# v1.net
KiCad netlist of a schematic drawn in EAGLE
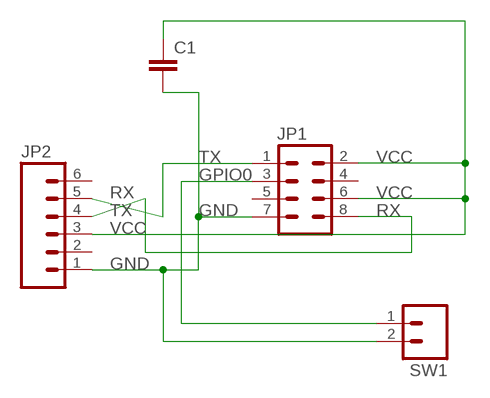
[diagram p0: schematic, sheet 1]

(export (version "E")
  (design (tool "Eeschema 10.0.6"))
  (components
    (comp (ref "C1")
      (value "CAP0805")
      (footprint "eagle-import:0805")
      (libsource (lib "eagle-import") (part "CAP0805"))
    )
    (comp (ref "JP1")
      (value "M04X2")
      (footprint "eagle-import:2X4")
      (libsource (lib "eagle-import") (part "M04X2"))
    )
    (comp (ref "JP2")
      (value "M06SILK_FEMALE_PTH")
      (footprint "eagle-import:1X06")
      (libsource (lib "eagle-import") (part "M06SILK_FEMALE_PTH"))
    )
    (comp (ref "SW1")
      (value "M02PTH")
      (footprint "eagle-import:1X02")
      (libsource (lib "eagle-import") (part "M02PTH"))
    )
  )
  (nets
    (net (code "1") (name "/GND") (class "Default")
      (node (ref "C1") (pin "2") (pinfunction "2_2") (pintype "passive"))
      (node (ref "JP1") (pin "7") (pinfunction "7_7") (pintype "passive"))
      (node (ref "JP2") (pin "1") (pinfunction "1_1") (pintype "passive"))
      (node (ref "SW1") (pin "2") (pinfunction "2_2") (pintype "passive"))
    )
    (net (code "2") (name "/GPIO0") (class "Default")
      (node (ref "JP1") (pin "3") (pinfunction "3_3") (pintype "passive"))
      (node (ref "SW1") (pin "1") (pinfunction "1_1") (pintype "passive"))
    )
    (net (code "3") (name "/RX") (class "Default")
      (node (ref "JP1") (pin "8") (pinfunction "8_8") (pintype "passive"))
      (node (ref "JP2") (pin "4") (pinfunction "4_4") (pintype "passive"))
    )
    (net (code "4") (name "/TX") (class "Default")
      (node (ref "JP1") (pin "1") (pinfunction "1_1") (pintype "passive"))
      (node (ref "JP2") (pin "5") (pinfunction "5_5") (pintype "passive"))
    )
    (net (code "5") (name "/VCC") (class "Default")
      (node (ref "C1") (pin "1") (pinfunction "1_1") (pintype "passive"))
      (node (ref "JP1") (pin "2") (pinfunction "2_2") (pintype "passive"))
      (node (ref "JP1") (pin "6") (pinfunction "6_6") (pintype "passive"))
      (node (ref "JP2") (pin "3") (pinfunction "3_3") (pintype "passive"))
    )
    (net (code "6") (name "unconnected-(JP1-Pad4)") (class "Default")
      (node (ref "JP1") (pin "4") (pinfunction "4_4") (pintype "passive"))
    )
    (net (code "7") (name "unconnected-(JP1-Pad5)") (class "Default")
      (node (ref "JP1") (pin "5") (pinfunction "5_5") (pintype "passive"))
    )
    (net (code "8") (name "unconnected-(JP2-Pad2)") (class "Default")
      (node (ref "JP2") (pin "2") (pinfunction "2_2") (pintype "passive"))
    )
    (net (code "9") (name "unconnected-(JP2-Pad6)") (class "Default")
      (node (ref "JP2") (pin "6") (pinfunction "6_6") (pintype "passive"))
    )
  )
)
